# PIC.net
KiCad netlist of a schematic drawn in Altium Designer
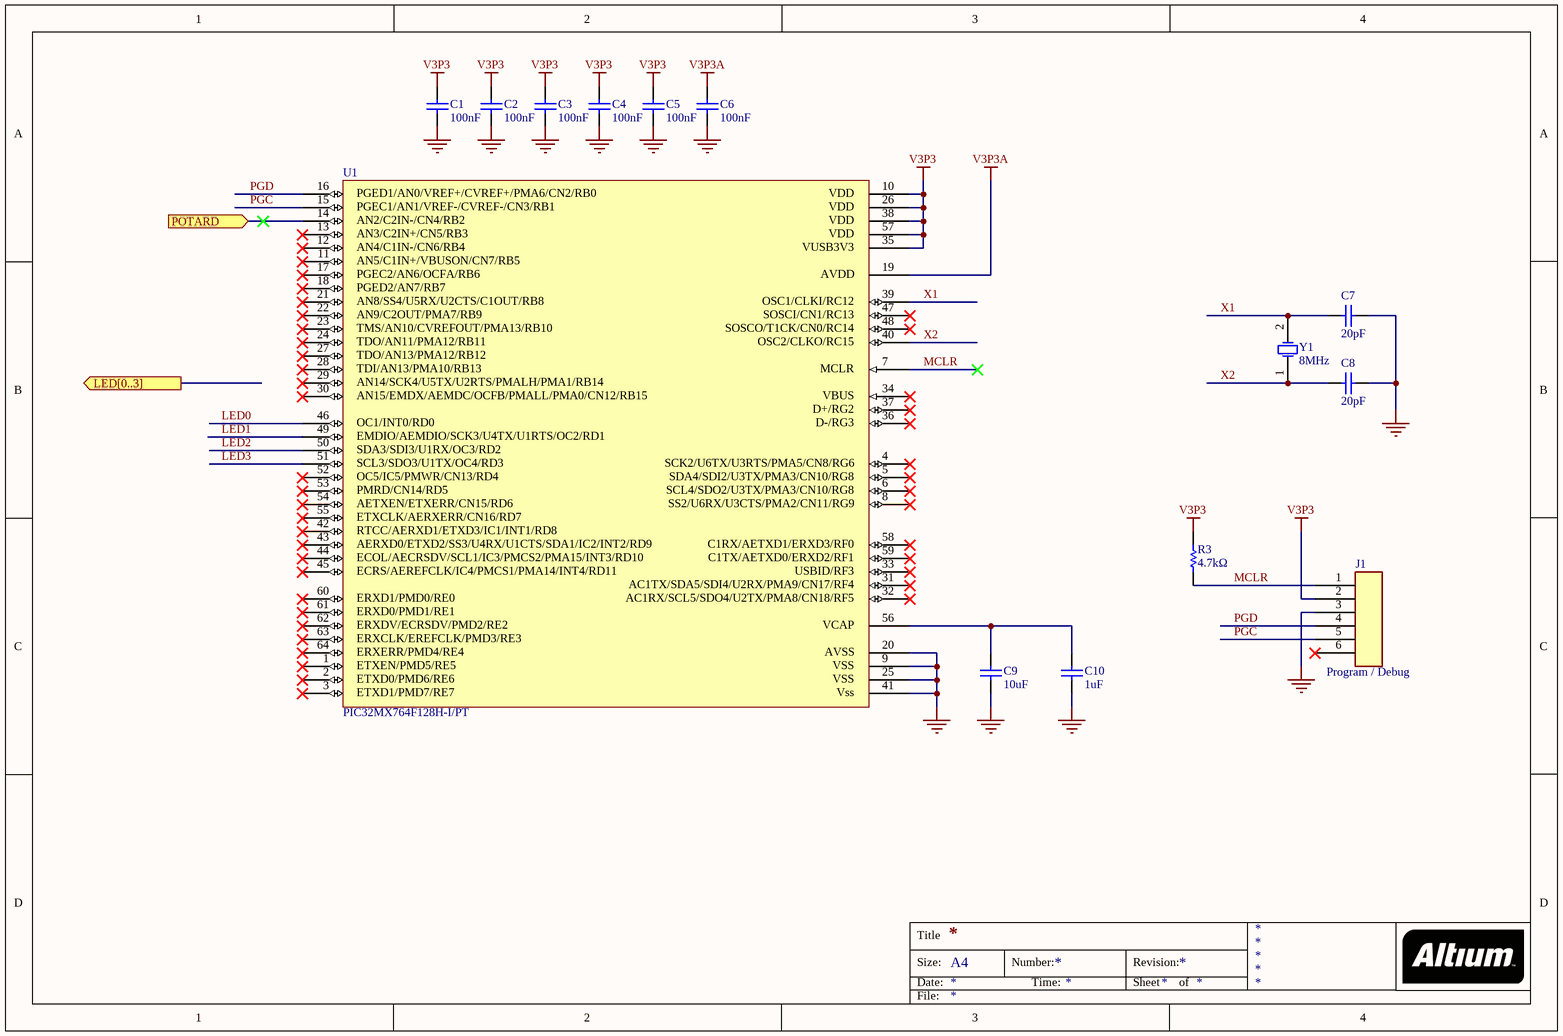
[diagram p0: PIC.SchDoc]

(export (version "E")
  (design (tool "Eeschema 10.0.6"))
  (components
    (comp (ref "C1")
      (value "100nF")
      (footprint "CAPC1608N")
      (description "Capacitor")
      (fields (field (name "PUBLISHER") "Altium Limited"))
      (libsource (lib "Miscellaneous Devices") (part "Cap"))
    )
    (comp (ref "C2")
      (value "100nF")
      (footprint "CAPC1608N")
      (description "Capacitor")
      (fields (field (name "PUBLISHER") "Altium Limited"))
      (libsource (lib "Miscellaneous Devices") (part "Cap"))
    )
    (comp (ref "C3")
      (value "100nF")
      (footprint "CAPC1608N")
      (description "Capacitor")
      (fields (field (name "PUBLISHER") "Altium Limited"))
      (libsource (lib "Miscellaneous Devices") (part "Cap"))
    )
    (comp (ref "C4")
      (value "100nF")
      (footprint "CAPC1608N")
      (description "Capacitor")
      (fields (field (name "PUBLISHER") "Altium Limited"))
      (libsource (lib "Miscellaneous Devices") (part "Cap"))
    )
    (comp (ref "C5")
      (value "100nF")
      (footprint "CAPC1608N")
      (description "Capacitor")
      (fields (field (name "PUBLISHER") "Altium Limited"))
      (libsource (lib "Miscellaneous Devices") (part "Cap"))
    )
    (comp (ref "C6")
      (value "100nF")
      (footprint "CAPC1608N")
      (description "Capacitor")
      (fields (field (name "PUBLISHER") "Altium Limited"))
      (libsource (lib "Miscellaneous Devices") (part "Cap"))
    )
    (comp (ref "C7")
      (value "20pF")
      (footprint "CAPC1005N")
      (description "Capacitor")
      (fields (field (name "PUBLISHER") "Altium Limited"))
      (libsource (lib "Miscellaneous Devices") (part "Cap"))
    )
    (comp (ref "C8")
      (value "20pF")
      (footprint "CAPC1005N")
      (description "Capacitor")
      (fields (field (name "PUBLISHER") "Altium Limited"))
      (libsource (lib "Miscellaneous Devices") (part "Cap"))
    )
    (comp (ref "C9")
      (value "10uF")
      (footprint "CAPC2012N")
      (description "Capacitor")
      (fields (field (name "PUBLISHER") "Altium Limited"))
      (libsource (lib "Miscellaneous Devices") (part "Cap"))
    )
    (comp (ref "C10")
      (value "1uF")
      (footprint "CAPC1608N")
      (description "Capacitor")
      (fields (field (name "PUBLISHER") "Altium Limited"))
      (libsource (lib "Miscellaneous Devices") (part "Cap"))
    )
    (comp (ref "J1") (value "Program / Debug") (libsource (lib "PIC") (part "CON6")))
    (comp (ref "R3")
      (value "4.7kΩ")
      (footprint "RESC1608N")
      (description "Resistor")
      (fields (field (name "PUBLISHER") "Altium Limited"))
      (libsource (lib "Miscellaneous Devices") (part "Res1"))
    )
    (comp (ref "U1")
      (value "PIC32MX764F128H-I/PT")
      (description "PIC32MX764F128H")
      (libsource (lib "PIC") (part "PIC32MX764F128H-I/PT"))
    )
    (comp (ref "Y1")
      (value "8MHz")
      (footprint "R38")
      (description "Crystal Oscillator")
      (fields (field (name "PUBLISHER") "Altium Limited"))
      (libsource (lib "Miscellaneous Devices") (part "XTAL"))
    )
  )
  (nets
    (net (code "1") (name "/LED0") (class "Default")
      (node (ref "U1") (pin "46") (pinfunction "46_46") (pintype "bidirectional"))
    )
    (net (code "2") (name "/LED1") (class "Default")
      (node (ref "U1") (pin "49") (pinfunction "49_49") (pintype "bidirectional"))
    )
    (net (code "3") (name "/LED2") (class "Default")
      (node (ref "U1") (pin "50") (pinfunction "50_50") (pintype "bidirectional"))
    )
    (net (code "4") (name "/LED3") (class "Default")
      (node (ref "U1") (pin "51") (pinfunction "51_51") (pintype "bidirectional"))
    )
    (net (code "6") (name "/MCLR") (class "Default")
      (node (ref "J1") (pin "1") (pinfunction "1_1") (pintype "power_in"))
      (node (ref "R3") (pin "1") (pinfunction "1_1") (pintype "passive"))
      (node (ref "U1") (pin "7") (pinfunction "7_7") (pintype "input"))
    )
    (net (code "7") (name "/PGC") (class "Default")
      (node (ref "J1") (pin "5") (pinfunction "5_5") (pintype "power_in"))
      (node (ref "U1") (pin "15") (pinfunction "15_15") (pintype "bidirectional"))
    )
    (net (code "8") (name "/PGD") (class "Default")
      (node (ref "J1") (pin "4") (pinfunction "4_4") (pintype "power_in"))
      (node (ref "U1") (pin "16") (pinfunction "16_16") (pintype "bidirectional"))
    )
    (net (code "9") (name "/POTARD") (class "Default")
      (node (ref "U1") (pin "14") (pinfunction "14_14") (pintype "bidirectional+no_connect"))
    )
    (net (code "10") (name "/X1") (class "Default")
      (node (ref "C7") (pin "1") (pinfunction "1_1") (pintype "passive"))
      (node (ref "U1") (pin "39") (pinfunction "39_39") (pintype "bidirectional"))
      (node (ref "Y1") (pin "2") (pinfunction "OSC2_2") (pintype "passive"))
    )
    (net (code "11") (name "/X2") (class "Default")
      (node (ref "C8") (pin "1") (pinfunction "1_1") (pintype "passive"))
      (node (ref "U1") (pin "40") (pinfunction "40_40") (pintype "bidirectional"))
      (node (ref "Y1") (pin "1") (pinfunction "OSC1_1") (pintype "passive"))
    )
    (net (code "12") (name "GND") (class "Default")
      (node (ref "C1") (pin "1") (pinfunction "1_1") (pintype "passive"))
      (node (ref "C10") (pin "1") (pinfunction "1_1") (pintype "passive"))
      (node (ref "C2") (pin "1") (pinfunction "1_1") (pintype "passive"))
      (node (ref "C3") (pin "1") (pinfunction "1_1") (pintype "passive"))
      (node (ref "C4") (pin "1") (pinfunction "1_1") (pintype "passive"))
      (node (ref "C5") (pin "1") (pinfunction "1_1") (pintype "passive"))
      (node (ref "C6") (pin "1") (pinfunction "1_1") (pintype "passive"))
      (node (ref "C7") (pin "2") (pinfunction "2_2") (pintype "passive"))
      (node (ref "C8") (pin "2") (pinfunction "2_2") (pintype "passive"))
      (node (ref "C9") (pin "1") (pinfunction "1_1") (pintype "passive"))
      (node (ref "J1") (pin "3") (pinfunction "3_3") (pintype "power_in"))
      (node (ref "U1") (pin "20") (pinfunction "20_20") (pintype "power_in"))
      (node (ref "U1") (pin "25") (pinfunction "25_25") (pintype "power_in"))
      (node (ref "U1") (pin "41") (pinfunction "41_41") (pintype "power_in"))
      (node (ref "U1") (pin "9") (pinfunction "9_9") (pintype "power_in"))
    )
    (net (code "13") (name "Net-(C10-Pad2)") (class "Default")
      (node (ref "C10") (pin "2") (pinfunction "2_2") (pintype "passive"))
      (node (ref "C9") (pin "2") (pinfunction "2_2") (pintype "passive"))
      (node (ref "U1") (pin "56") (pinfunction "56_56") (pintype "power_in"))
    )
    (net (code "14") (name "V3P3") (class "Default")
      (node (ref "C1") (pin "2") (pinfunction "2_2") (pintype "passive"))
      (node (ref "C2") (pin "2") (pinfunction "2_2") (pintype "passive"))
      (node (ref "C3") (pin "2") (pinfunction "2_2") (pintype "passive"))
      (node (ref "C4") (pin "2") (pinfunction "2_2") (pintype "passive"))
      (node (ref "C5") (pin "2") (pinfunction "2_2") (pintype "passive"))
      (node (ref "J1") (pin "2") (pinfunction "2_2") (pintype "power_in"))
      (node (ref "R3") (pin "2") (pinfunction "2_2") (pintype "passive"))
      (node (ref "U1") (pin "10") (pinfunction "10_10") (pintype "power_in"))
      (node (ref "U1") (pin "26") (pinfunction "26_26") (pintype "power_in"))
      (node (ref "U1") (pin "35") (pinfunction "35_35") (pintype "power_in"))
      (node (ref "U1") (pin "38") (pinfunction "38_38") (pintype "power_in"))
      (node (ref "U1") (pin "57") (pinfunction "57_57") (pintype "power_in"))
    )
    (net (code "15") (name "V3P3A") (class "Default")
      (node (ref "C6") (pin "2") (pinfunction "2_2") (pintype "passive"))
      (node (ref "U1") (pin "19") (pinfunction "19_19") (pintype "power_in"))
    )
    (net (code "16") (name "unconnected-(J1-Pad6)") (class "Default")
      (node (ref "J1") (pin "6") (pinfunction "6_6") (pintype "power_in+no_connect"))
    )
    (net (code "17") (name "unconnected-(U1-Pad1)") (class "Default")
      (node (ref "U1") (pin "1") (pinfunction "1_1") (pintype "bidirectional+no_connect"))
    )
    (net (code "18") (name "unconnected-(U1-Pad2)") (class "Default")
      (node (ref "U1") (pin "2") (pinfunction "2_2") (pintype "bidirectional+no_connect"))
    )
    (net (code "19") (name "unconnected-(U1-Pad3)") (class "Default")
      (node (ref "U1") (pin "3") (pinfunction "3_3") (pintype "bidirectional+no_connect"))
    )
    (net (code "20") (name "unconnected-(U1-Pad4)") (class "Default")
      (node (ref "U1") (pin "4") (pinfunction "4_4") (pintype "bidirectional+no_connect"))
    )
    (net (code "21") (name "unconnected-(U1-Pad5)") (class "Default")
      (node (ref "U1") (pin "5") (pinfunction "5_5") (pintype "bidirectional+no_connect"))
    )
    (net (code "22") (name "unconnected-(U1-Pad6)") (class "Default")
      (node (ref "U1") (pin "6") (pinfunction "6_6") (pintype "bidirectional+no_connect"))
    )
    (net (code "23") (name "unconnected-(U1-Pad8)") (class "Default")
      (node (ref "U1") (pin "8") (pinfunction "8_8") (pintype "bidirectional+no_connect"))
    )
    (net (code "24") (name "unconnected-(U1-Pad11)") (class "Default")
      (node (ref "U1") (pin "11") (pinfunction "11_11") (pintype "bidirectional+no_connect"))
    )
    (net (code "25") (name "unconnected-(U1-Pad12)") (class "Default")
      (node (ref "U1") (pin "12") (pinfunction "12_12") (pintype "bidirectional+no_connect"))
    )
    (net (code "26") (name "unconnected-(U1-Pad13)") (class "Default")
      (node (ref "U1") (pin "13") (pinfunction "13_13") (pintype "bidirectional+no_connect"))
    )
    (net (code "27") (name "unconnected-(U1-Pad17)") (class "Default")
      (node (ref "U1") (pin "17") (pinfunction "17_17") (pintype "bidirectional+no_connect"))
    )
    (net (code "28") (name "unconnected-(U1-Pad18)") (class "Default")
      (node (ref "U1") (pin "18") (pinfunction "18_18") (pintype "bidirectional+no_connect"))
    )
    (net (code "29") (name "unconnected-(U1-Pad21)") (class "Default")
      (node (ref "U1") (pin "21") (pinfunction "21_21") (pintype "bidirectional+no_connect"))
    )
    (net (code "30") (name "unconnected-(U1-Pad22)") (class "Default")
      (node (ref "U1") (pin "22") (pinfunction "22_22") (pintype "bidirectional+no_connect"))
    )
    (net (code "31") (name "unconnected-(U1-Pad23)") (class "Default")
      (node (ref "U1") (pin "23") (pinfunction "23_23") (pintype "bidirectional+no_connect"))
    )
    (net (code "32") (name "unconnected-(U1-Pad24)") (class "Default")
      (node (ref "U1") (pin "24") (pinfunction "24_24") (pintype "bidirectional+no_connect"))
    )
    (net (code "33") (name "unconnected-(U1-Pad27)") (class "Default")
      (node (ref "U1") (pin "27") (pinfunction "27_27") (pintype "bidirectional+no_connect"))
    )
    (net (code "34") (name "unconnected-(U1-Pad28)") (class "Default")
      (node (ref "U1") (pin "28") (pinfunction "28_28") (pintype "bidirectional+no_connect"))
    )
    (net (code "35") (name "unconnected-(U1-Pad29)") (class "Default")
      (node (ref "U1") (pin "29") (pinfunction "29_29") (pintype "bidirectional+no_connect"))
    )
    (net (code "36") (name "unconnected-(U1-Pad30)") (class "Default")
      (node (ref "U1") (pin "30") (pinfunction "30_30") (pintype "bidirectional+no_connect"))
    )
    (net (code "37") (name "unconnected-(U1-Pad31)") (class "Default")
      (node (ref "U1") (pin "31") (pinfunction "31_31") (pintype "bidirectional+no_connect"))
    )
    (net (code "38") (name "unconnected-(U1-Pad32)") (class "Default")
      (node (ref "U1") (pin "32") (pinfunction "32_32") (pintype "bidirectional+no_connect"))
    )
    (net (code "39") (name "unconnected-(U1-Pad33)") (class "Default")
      (node (ref "U1") (pin "33") (pinfunction "33_33") (pintype "bidirectional+no_connect"))
    )
    (net (code "40") (name "unconnected-(U1-Pad34)") (class "Default")
      (node (ref "U1") (pin "34") (pinfunction "34_34") (pintype "input+no_connect"))
    )
    (net (code "41") (name "unconnected-(U1-Pad36)") (class "Default")
      (node (ref "U1") (pin "36") (pinfunction "36_36") (pintype "bidirectional+no_connect"))
    )
    (net (code "42") (name "unconnected-(U1-Pad37)") (class "Default")
      (node (ref "U1") (pin "37") (pinfunction "37_37") (pintype "bidirectional+no_connect"))
    )
    (net (code "43") (name "unconnected-(U1-Pad42)") (class "Default")
      (node (ref "U1") (pin "42") (pinfunction "42_42") (pintype "bidirectional+no_connect"))
    )
    (net (code "44") (name "unconnected-(U1-Pad43)") (class "Default")
      (node (ref "U1") (pin "43") (pinfunction "43_43") (pintype "bidirectional+no_connect"))
    )
    (net (code "45") (name "unconnected-(U1-Pad44)") (class "Default")
      (node (ref "U1") (pin "44") (pinfunction "44_44") (pintype "bidirectional+no_connect"))
    )
    (net (code "46") (name "unconnected-(U1-Pad45)") (class "Default")
      (node (ref "U1") (pin "45") (pinfunction "45_45") (pintype "bidirectional+no_connect"))
    )
    (net (code "47") (name "unconnected-(U1-Pad47)") (class "Default")
      (node (ref "U1") (pin "47") (pinfunction "47_47") (pintype "bidirectional+no_connect"))
    )
    (net (code "48") (name "unconnected-(U1-Pad48)") (class "Default")
      (node (ref "U1") (pin "48") (pinfunction "48_48") (pintype "bidirectional+no_connect"))
    )
    (net (code "49") (name "unconnected-(U1-Pad52)") (class "Default")
      (node (ref "U1") (pin "52") (pinfunction "52_52") (pintype "bidirectional+no_connect"))
    )
    (net (code "50") (name "unconnected-(U1-Pad53)") (class "Default")
      (node (ref "U1") (pin "53") (pinfunction "53_53") (pintype "bidirectional+no_connect"))
    )
    (net (code "51") (name "unconnected-(U1-Pad54)") (class "Default")
      (node (ref "U1") (pin "54") (pinfunction "54_54") (pintype "bidirectional+no_connect"))
    )
    (net (code "52") (name "unconnected-(U1-Pad55)") (class "Default")
      (node (ref "U1") (pin "55") (pinfunction "55_55") (pintype "bidirectional+no_connect"))
    )
    (net (code "53") (name "unconnected-(U1-Pad58)") (class "Default")
      (node (ref "U1") (pin "58") (pinfunction "58_58") (pintype "bidirectional+no_connect"))
    )
    (net (code "54") (name "unconnected-(U1-Pad59)") (class "Default")
      (node (ref "U1") (pin "59") (pinfunction "59_59") (pintype "bidirectional+no_connect"))
    )
    (net (code "55") (name "unconnected-(U1-Pad60)") (class "Default")
      (node (ref "U1") (pin "60") (pinfunction "60_60") (pintype "bidirectional+no_connect"))
    )
    (net (code "56") (name "unconnected-(U1-Pad61)") (class "Default")
      (node (ref "U1") (pin "61") (pinfunction "61_61") (pintype "bidirectional+no_connect"))
    )
    (net (code "57") (name "unconnected-(U1-Pad62)") (class "Default")
      (node (ref "U1") (pin "62") (pinfunction "62_62") (pintype "bidirectional+no_connect"))
    )
    (net (code "58") (name "unconnected-(U1-Pad63)") (class "Default")
      (node (ref "U1") (pin "63") (pinfunction "63_63") (pintype "bidirectional+no_connect"))
    )
    (net (code "59") (name "unconnected-(U1-Pad64)") (class "Default")
      (node (ref "U1") (pin "64") (pinfunction "64_64") (pintype "bidirectional+no_connect"))
    )
  )
)
